# PCB_design_2021-05-29.net
KiCad netlist of a schematic drawn in EasyEDA
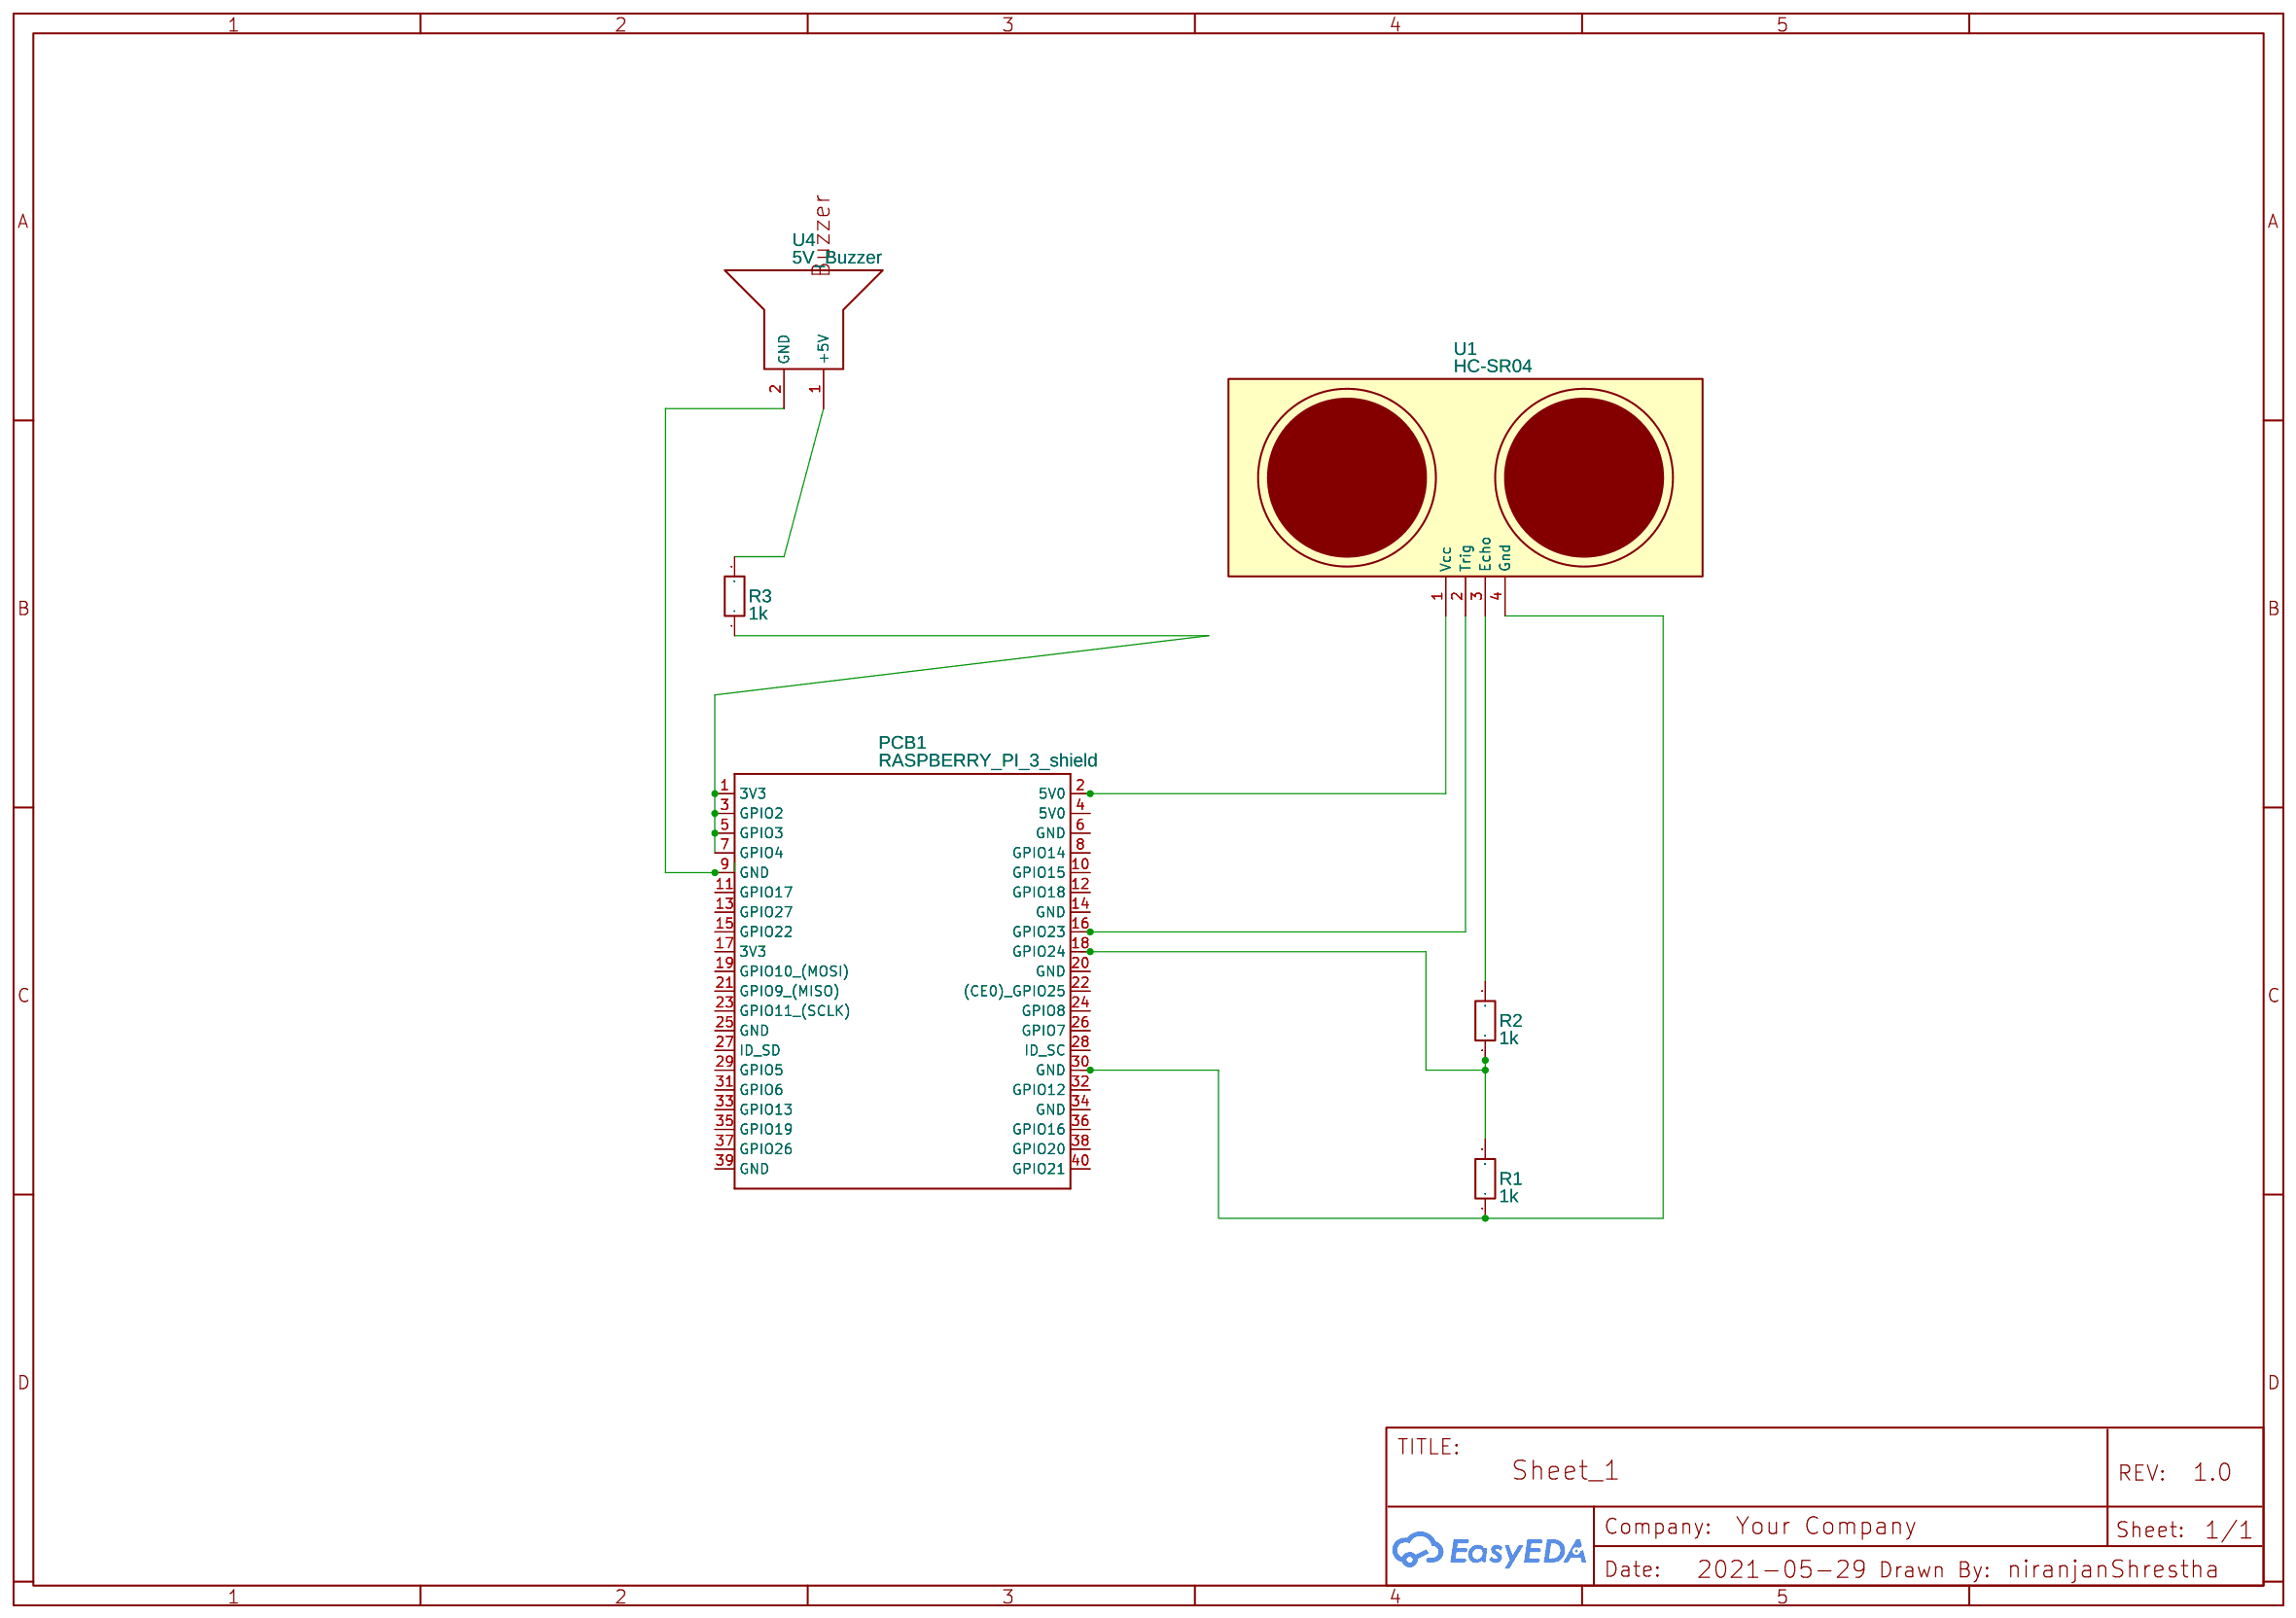
[diagram p0: schematic sheet]

(export (version "E")
  (design (tool "Eeschema 10.0.6"))
  (components
    (comp (ref "PCB1") (value "RASPBERRY_PI_3_shield") (libsource (lib "") (part "RASPBERRY_PI_3_shield")))
    (comp (ref "R1") (value "1k") (libsource (lib "") (part "R_0201_EU")))
    (comp (ref "R2") (value "1k") (libsource (lib "") (part "R_0201_EU")))
    (comp (ref "R3") (value "1k") (libsource (lib "") (part "R_0201_EU")))
    (comp (ref "U1") (value "HC-SR04") (libsource (lib "") (part "HC-SR04")))
    (comp (ref "U4")
      (value "5V_Buzzer")
      (fields (field (name "BOM_Manufacturer Part") "HN9650B"))
      (libsource (lib "") (part "5V_Buzzer"))
    )
  )
  (nets
    (net (code "1") (name "Net-(PCB1-GPIO2)") (class "Default")
      (node (ref "PCB1") (pin "1") (pinfunction "3V3_1") (pintype "unspecified"))
      (node (ref "PCB1") (pin "3") (pinfunction "GPIO2_3") (pintype "unspecified"))
      (node (ref "PCB1") (pin "5") (pinfunction "GPIO3_5") (pintype "unspecified"))
      (node (ref "PCB1") (pin "7") (pinfunction "GPIO4_7") (pintype "unspecified"))
      (node (ref "R3") (pin "1") (pinfunction "1_1") (pintype "unspecified"))
    )
    (net (code "2") (name "Net-(PCB1-GPIO23)") (class "Default")
      (node (ref "PCB1") (pin "16") (pinfunction "GPIO23_16") (pintype "unspecified"))
      (node (ref "U1") (pin "2") (pinfunction "Trig_2") (pintype "unspecified"))
    )
    (net (code "3") (name "Net-(PCB1-GPIO24)") (class "Default")
      (node (ref "PCB1") (pin "18") (pinfunction "GPIO24_18") (pintype "unspecified"))
      (node (ref "R1") (pin "2") (pinfunction "2_2") (pintype "unspecified"))
      (node (ref "R2") (pin "1") (pinfunction "1_1") (pintype "unspecified"))
    )
    (net (code "4") (name "Net-(U1-Echo)") (class "Default")
      (node (ref "R2") (pin "2") (pinfunction "2_2") (pintype "unspecified"))
      (node (ref "U1") (pin "3") (pinfunction "Echo_3") (pintype "unspecified"))
    )
    (net (code "5") (name "Net-(U1-Gnd)") (class "Default")
      (node (ref "PCB1") (pin "30") (pinfunction "GND_30") (pintype "unspecified"))
      (node (ref "R1") (pin "1") (pinfunction "1_1") (pintype "unspecified"))
      (node (ref "U1") (pin "4") (pinfunction "Gnd_4") (pintype "unspecified"))
    )
    (net (code "6") (name "Net-(U1-Vcc)") (class "Default")
      (node (ref "PCB1") (pin "2") (pinfunction "5V0_2") (pintype "unspecified"))
      (node (ref "U1") (pin "1") (pinfunction "Vcc_1") (pintype "unspecified"))
    )
    (net (code "7") (name "Net-(U4-+5V)") (class "Default")
      (node (ref "R3") (pin "2") (pinfunction "2_2") (pintype "unspecified"))
      (node (ref "U4") (pin "1") (pinfunction "+5V_1") (pintype "unspecified"))
    )
    (net (code "8") (name "Net-(U4-GND)") (class "Default")
      (node (ref "PCB1") (pin "9") (pinfunction "GND_9") (pintype "unspecified"))
      (node (ref "U4") (pin "2") (pinfunction "GND_2") (pintype "unspecified"))
    )
    (net (code "9") (name "unconnected-(PCB1-(CE0)_GPIO25-Pad22)") (class "Default")
      (node (ref "PCB1") (pin "22") (pinfunction "(CE0)_GPIO25_22") (pintype "unspecified"))
    )
    (net (code "10") (name "unconnected-(PCB1-3V3-Pad17)") (class "Default")
      (node (ref "PCB1") (pin "17") (pinfunction "3V3_17") (pintype "unspecified"))
    )
    (net (code "11") (name "unconnected-(PCB1-5V0-Pad4)") (class "Default")
      (node (ref "PCB1") (pin "4") (pinfunction "5V0_4") (pintype "unspecified"))
    )
    (net (code "12") (name "unconnected-(PCB1-GND-Pad6)") (class "Default")
      (node (ref "PCB1") (pin "6") (pinfunction "GND_6") (pintype "unspecified"))
    )
    (net (code "13") (name "unconnected-(PCB1-GND-Pad14)") (class "Default")
      (node (ref "PCB1") (pin "14") (pinfunction "GND_14") (pintype "unspecified"))
    )
    (net (code "14") (name "unconnected-(PCB1-GND-Pad20)") (class "Default")
      (node (ref "PCB1") (pin "20") (pinfunction "GND_20") (pintype "unspecified"))
    )
    (net (code "15") (name "unconnected-(PCB1-GND-Pad25)") (class "Default")
      (node (ref "PCB1") (pin "25") (pinfunction "GND_25") (pintype "unspecified"))
    )
    (net (code "16") (name "unconnected-(PCB1-GND-Pad34)") (class "Default")
      (node (ref "PCB1") (pin "34") (pinfunction "GND_34") (pintype "unspecified"))
    )
    (net (code "17") (name "unconnected-(PCB1-GND-Pad39)") (class "Default")
      (node (ref "PCB1") (pin "39") (pinfunction "GND_39") (pintype "unspecified"))
    )
    (net (code "18") (name "unconnected-(PCB1-GPIO5-Pad29)") (class "Default")
      (node (ref "PCB1") (pin "29") (pinfunction "GPIO5_29") (pintype "unspecified"))
    )
    (net (code "19") (name "unconnected-(PCB1-GPIO6-Pad31)") (class "Default")
      (node (ref "PCB1") (pin "31") (pinfunction "GPIO6_31") (pintype "unspecified"))
    )
    (net (code "20") (name "unconnected-(PCB1-GPIO7-Pad26)") (class "Default")
      (node (ref "PCB1") (pin "26") (pinfunction "GPIO7_26") (pintype "unspecified"))
    )
    (net (code "21") (name "unconnected-(PCB1-GPIO8-Pad24)") (class "Default")
      (node (ref "PCB1") (pin "24") (pinfunction "GPIO8_24") (pintype "unspecified"))
    )
    (net (code "22") (name "unconnected-(PCB1-GPIO9_(MISO)-Pad21)") (class "Default")
      (node (ref "PCB1") (pin "21") (pinfunction "GPIO9_(MISO)_21") (pintype "unspecified"))
    )
    (net (code "23") (name "unconnected-(PCB1-GPIO10_(MOSI)-Pad19)") (class "Default")
      (node (ref "PCB1") (pin "19") (pinfunction "GPIO10_(MOSI)_19") (pintype "unspecified"))
    )
    (net (code "24") (name "unconnected-(PCB1-GPIO11_(SCLK)-Pad23)") (class "Default")
      (node (ref "PCB1") (pin "23") (pinfunction "GPIO11_(SCLK)_23") (pintype "unspecified"))
    )
    (net (code "25") (name "unconnected-(PCB1-GPIO12-Pad32)") (class "Default")
      (node (ref "PCB1") (pin "32") (pinfunction "GPIO12_32") (pintype "unspecified"))
    )
    (net (code "26") (name "unconnected-(PCB1-GPIO13-Pad33)") (class "Default")
      (node (ref "PCB1") (pin "33") (pinfunction "GPIO13_33") (pintype "unspecified"))
    )
    (net (code "27") (name "unconnected-(PCB1-GPIO14-Pad8)") (class "Default")
      (node (ref "PCB1") (pin "8") (pinfunction "GPIO14_8") (pintype "unspecified"))
    )
    (net (code "28") (name "unconnected-(PCB1-GPIO15-Pad10)") (class "Default")
      (node (ref "PCB1") (pin "10") (pinfunction "GPIO15_10") (pintype "unspecified"))
    )
    (net (code "29") (name "unconnected-(PCB1-GPIO16-Pad36)") (class "Default")
      (node (ref "PCB1") (pin "36") (pinfunction "GPIO16_36") (pintype "unspecified"))
    )
    (net (code "30") (name "unconnected-(PCB1-GPIO17-Pad11)") (class "Default")
      (node (ref "PCB1") (pin "11") (pinfunction "GPIO17_11") (pintype "unspecified"))
    )
    (net (code "31") (name "unconnected-(PCB1-GPIO18-Pad12)") (class "Default")
      (node (ref "PCB1") (pin "12") (pinfunction "GPIO18_12") (pintype "unspecified"))
    )
    (net (code "32") (name "unconnected-(PCB1-GPIO19-Pad35)") (class "Default")
      (node (ref "PCB1") (pin "35") (pinfunction "GPIO19_35") (pintype "unspecified"))
    )
    (net (code "33") (name "unconnected-(PCB1-GPIO20-Pad38)") (class "Default")
      (node (ref "PCB1") (pin "38") (pinfunction "GPIO20_38") (pintype "unspecified"))
    )
    (net (code "34") (name "unconnected-(PCB1-GPIO21-Pad40)") (class "Default")
      (node (ref "PCB1") (pin "40") (pinfunction "GPIO21_40") (pintype "unspecified"))
    )
    (net (code "35") (name "unconnected-(PCB1-GPIO22-Pad15)") (class "Default")
      (node (ref "PCB1") (pin "15") (pinfunction "GPIO22_15") (pintype "unspecified"))
    )
    (net (code "36") (name "unconnected-(PCB1-GPIO26-Pad37)") (class "Default")
      (node (ref "PCB1") (pin "37") (pinfunction "GPIO26_37") (pintype "unspecified"))
    )
    (net (code "37") (name "unconnected-(PCB1-GPIO27-Pad13)") (class "Default")
      (node (ref "PCB1") (pin "13") (pinfunction "GPIO27_13") (pintype "unspecified"))
    )
    (net (code "38") (name "unconnected-(PCB1-ID_SC-Pad28)") (class "Default")
      (node (ref "PCB1") (pin "28") (pinfunction "ID_SC_28") (pintype "unspecified"))
    )
    (net (code "39") (name "unconnected-(PCB1-ID_SD-Pad27)") (class "Default")
      (node (ref "PCB1") (pin "27") (pinfunction "ID_SD_27") (pintype "unspecified"))
    )
  )
)
